# 4_Codec.net
KiCad netlist of a schematic drawn in Altium Designer
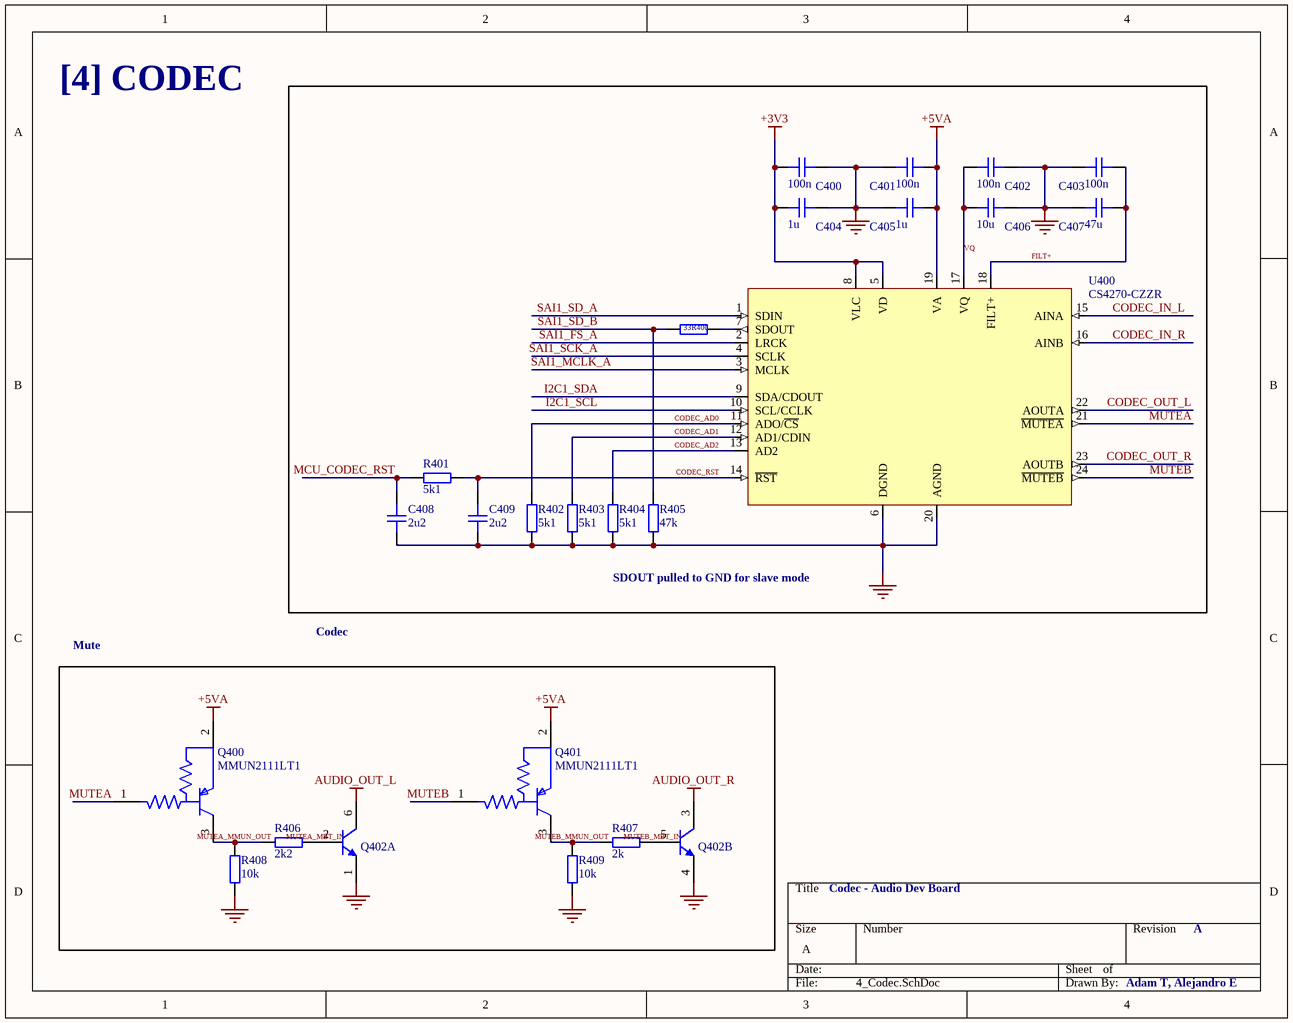
[diagram p0: 4_Codec.SchDoc]

(export (version "E")
  (design (tool "Eeschema 10.0.6"))
  (components
    (comp (ref "C400")
      (value "100n")
      (footprint "CAP_0402")
      (description "Capacitor SMD 0402")
      (libsource (lib "Schematic-Lib-PhilsLab") (part "CAP_0402"))
    )
    (comp (ref "C401")
      (value "100n")
      (footprint "CAP_0402")
      (description "Capacitor SMD 0402")
      (libsource (lib "Schematic-Lib-PhilsLab") (part "CAP_0402"))
    )
    (comp (ref "C402")
      (value "100n")
      (footprint "CAP_0402")
      (description "Capacitor SMD 0402")
      (libsource (lib "Schematic-Lib-PhilsLab") (part "CAP_0402"))
    )
    (comp (ref "C403")
      (value "100n")
      (footprint "CAP_0402")
      (description "Capacitor SMD 0402")
      (libsource (lib "Schematic-Lib-PhilsLab") (part "CAP_0402"))
    )
    (comp (ref "C404")
      (value "1u")
      (footprint "CAP_0603")
      (description "Capacitor SMD 0603")
      (libsource (lib "Schematic-Lib-PhilsLab") (part "CAP_0603"))
    )
    (comp (ref "C405")
      (value "1u")
      (footprint "CAP_0603")
      (description "Capacitor SMD 0603")
      (libsource (lib "Schematic-Lib-PhilsLab") (part "CAP_0603"))
    )
    (comp (ref "C406")
      (value "10u")
      (footprint "CAP_0603")
      (description "Capacitor SMD 0603")
      (libsource (lib "Schematic-Lib-PhilsLab") (part "CAP_0603"))
    )
    (comp (ref "C407")
      (value "47u")
      (footprint "CAP_1210")
      (description "Capacitor SMD 1210")
      (libsource (lib "Schematic-Lib-PhilsLab") (part "CAP_1210"))
    )
    (comp (ref "C408")
      (value "2u2")
      (footprint "CAP_0402")
      (description "Capacitor SMD 0402")
      (libsource (lib "Schematic-Lib-PhilsLab") (part "CAP_0402"))
    )
    (comp (ref "C409")
      (value "2u2")
      (footprint "CAP_0402")
      (description "Capacitor SMD 0402")
      (libsource (lib "Schematic-Lib-PhilsLab") (part "CAP_0402"))
    )
    (comp (ref "Q400")
      (value "MMUN2111LT1")
      (footprint "FP-318-08-MFG")
      (fields (field (name "VOLTAGE") "50V"))
      (libsource (lib "Altium Content Vault") (part "aca216ee67291743a5ff38348a4aab0"))
    )
    (comp (ref "Q401")
      (value "MMUN2111LT1")
      (footprint "FP-318-08-MFG")
      (fields (field (name "VOLTAGE") "50V"))
      (libsource (lib "Altium Content Vault") (part "aca216ee67291743a5ff38348a4aab0"))
    )
    (comp (ref "Q402")
      (value "MBT3904DW1T1G")
      (footprint "ONSC-SOT-363-6-419B-02_W_V")
      (description "Dual General Purpose Transistors, 6-Pin SOT-363, Pb-Free, Tape and Reel")
      (fields (field (name "MANUFACTURER") "On Semiconductor"))
      (libsource (lib "Altium Content Vault") (part "ONSC-NPN_NPN-6_F"))
    )
    (comp (ref "R400")
      (value "33")
      (footprint "RES_0402")
      (description "Resistor SMD 0402")
      (libsource (lib "Schematic-Lib-PhilsLab") (part "RES_0402"))
    )
    (comp (ref "R401")
      (value "5k1")
      (footprint "RES_0402")
      (description "Resistor SMD 0402")
      (libsource (lib "Schematic-Lib-PhilsLab") (part "RES_0402"))
    )
    (comp (ref "R402")
      (value "5k1")
      (footprint "RES_0402")
      (description "Resistor SMD 0402")
      (libsource (lib "Schematic-Lib-PhilsLab") (part "RES_0402"))
    )
    (comp (ref "R403")
      (value "5k1")
      (footprint "RES_0402")
      (description "Resistor SMD 0402")
      (libsource (lib "Schematic-Lib-PhilsLab") (part "RES_0402"))
    )
    (comp (ref "R404")
      (value "5k1")
      (footprint "RES_0402")
      (description "Resistor SMD 0402")
      (libsource (lib "Schematic-Lib-PhilsLab") (part "RES_0402"))
    )
    (comp (ref "R405")
      (value "47k")
      (footprint "RES_0402")
      (description "Resistor SMD 0402")
      (libsource (lib "Schematic-Lib-PhilsLab") (part "RES_0402"))
    )
    (comp (ref "R406")
      (value "2k2")
      (footprint "RES_0402")
      (description "Resistor SMD 0402")
      (libsource (lib "Schematic-Lib-PhilsLab") (part "RES_0402"))
    )
    (comp (ref "R407")
      (value "2k")
      (footprint "RES_0402")
      (description "Resistor SMD 0402")
      (libsource (lib "Schematic-Lib-PhilsLab") (part "RES_0402"))
    )
    (comp (ref "R408")
      (value "10k")
      (footprint "RES_0402")
      (description "Resistor SMD 0402")
      (libsource (lib "Schematic-Lib-PhilsLab") (part "RES_0402"))
    )
    (comp (ref "R409")
      (value "10k")
      (footprint "RES_0402")
      (description "Resistor SMD 0402")
      (libsource (lib "Schematic-Lib-PhilsLab") (part "RES_0402"))
    )
    (comp (ref "U400")
      (value "CS4270-CZZR")
      (footprint "TSSOP-24")
      (description "24-Bit 192kHz Stereo Audio Codec TSSOP-24")
      (fields (field (name "MANUFACTURER") "Cirrus Logic"))
      (libsource (lib "Schematic-Lib-PhilsLab") (part "CS4270-CZZR"))
    )
  )
  (nets
    (net (code "1") (name "+3V3") (class "Default")
      (node (ref "C400") (pin "1") (pinfunction "1_1") (pintype "passive"))
      (node (ref "C404") (pin "2") (pinfunction "2_2") (pintype "passive"))
      (node (ref "U400") (pin "5") (pinfunction "VD_5") (pintype "power_in"))
      (node (ref "U400") (pin "8") (pinfunction "VLC_8") (pintype "power_in"))
    )
    (net (code "2") (name "+5VA") (class "Default")
      (node (ref "C401") (pin "1") (pinfunction "1_1") (pintype "passive"))
      (node (ref "C405") (pin "2") (pinfunction "2_2") (pintype "passive"))
      (node (ref "Q400") (pin "2") (pinfunction "E_2") (pintype "passive"))
      (node (ref "Q401") (pin "2") (pinfunction "E_2") (pintype "passive"))
      (node (ref "U400") (pin "19") (pinfunction "VA_19") (pintype "power_in"))
    )
    (net (code "3") (name "/CODEC_AD0") (class "Default")
      (node (ref "R402") (pin "2") (pinfunction "2_2") (pintype "passive"))
      (node (ref "U400") (pin "11") (pinfunction "ADO/~{CS}_11") (pintype "input"))
    )
    (net (code "4") (name "/CODEC_AD1") (class "Default")
      (node (ref "R403") (pin "2") (pinfunction "2_2") (pintype "passive"))
      (node (ref "U400") (pin "12") (pinfunction "AD1/CDIN_12") (pintype "input"))
    )
    (net (code "5") (name "/CODEC_AD2") (class "Default")
      (node (ref "R404") (pin "2") (pinfunction "2_2") (pintype "passive"))
      (node (ref "U400") (pin "13") (pinfunction "AD2_13") (pintype "passive"))
    )
    (net (code "6") (name "/CODEC_IN_L") (class "Default")
      (node (ref "U400") (pin "15") (pinfunction "AINA_15") (pintype "input"))
    )
    (net (code "7") (name "/CODEC_IN_R") (class "Default")
      (node (ref "U400") (pin "16") (pinfunction "AINB_16") (pintype "input"))
    )
    (net (code "8") (name "/CODEC_OUT_L") (class "Default")
      (node (ref "U400") (pin "22") (pinfunction "AOUTA_22") (pintype "output"))
    )
    (net (code "9") (name "/CODEC_OUT_R") (class "Default")
      (node (ref "U400") (pin "23") (pinfunction "AOUTB_23") (pintype "output"))
    )
    (net (code "10") (name "/CODEC_RST") (class "Default")
      (node (ref "C409") (pin "2") (pinfunction "2_2") (pintype "passive"))
      (node (ref "R401") (pin "1") (pinfunction "1_1") (pintype "passive"))
      (node (ref "U400") (pin "14") (pinfunction "~{RST}_14") (pintype "input"))
    )
    (net (code "11") (name "/FILT+") (class "Default")
      (node (ref "C403") (pin "1") (pinfunction "1_1") (pintype "passive"))
      (node (ref "C407") (pin "2") (pinfunction "2_2") (pintype "passive"))
      (node (ref "U400") (pin "18") (pinfunction "FILT+_18") (pintype "power_in"))
    )
    (net (code "12") (name "/I2C1_SCL") (class "Default")
      (node (ref "U400") (pin "10") (pinfunction "SCL/CCLK_10") (pintype "input"))
    )
    (net (code "13") (name "/I2C1_SDA") (class "Default")
      (node (ref "U400") (pin "9") (pinfunction "SDA/CDOUT_9") (pintype "bidirectional"))
    )
    (net (code "14") (name "/MCU_CODEC_RST") (class "Default")
      (node (ref "C408") (pin "2") (pinfunction "2_2") (pintype "passive"))
      (node (ref "R401") (pin "2") (pinfunction "2_2") (pintype "passive"))
    )
    (net (code "15") (name "/MUTEA") (class "Default")
      (node (ref "Q400") (pin "1") (pinfunction "B_1") (pintype "passive"))
      (node (ref "U400") (pin "21") (pinfunction "~{MUTEA}_21") (pintype "output"))
    )
    (net (code "16") (name "/MUTEA_MBT_IN") (class "Default")
      (node (ref "Q402") (pin "2") (pinfunction "B_2") (pintype "passive"))
      (node (ref "R406") (pin "2") (pinfunction "2_2") (pintype "passive"))
    )
    (net (code "17") (name "/MUTEA_MMUN_OUT") (class "Default")
      (node (ref "Q400") (pin "3") (pinfunction "C_3") (pintype "passive"))
      (node (ref "R406") (pin "1") (pinfunction "1_1") (pintype "passive"))
      (node (ref "R408") (pin "2") (pinfunction "2_2") (pintype "passive"))
    )
    (net (code "18") (name "/MUTEB") (class "Default")
      (node (ref "Q401") (pin "1") (pinfunction "B_1") (pintype "passive"))
      (node (ref "U400") (pin "24") (pinfunction "~{MUTEB}_24") (pintype "output"))
    )
    (net (code "19") (name "/MUTEB_MBT_IN") (class "Default")
      (node (ref "Q402") (pin "5") (pinfunction "B_5") (pintype "passive"))
      (node (ref "R407") (pin "2") (pinfunction "2_2") (pintype "passive"))
    )
    (net (code "20") (name "/MUTEB_MMUN_OUT") (class "Default")
      (node (ref "Q401") (pin "3") (pinfunction "C_3") (pintype "passive"))
      (node (ref "R407") (pin "1") (pinfunction "1_1") (pintype "passive"))
      (node (ref "R409") (pin "2") (pinfunction "2_2") (pintype "passive"))
    )
    (net (code "21") (name "/SAI1_FS_A") (class "Default")
      (node (ref "U400") (pin "2") (pinfunction "LRCK_2") (pintype "bidirectional"))
    )
    (net (code "22") (name "/SAI1_MCLK_A") (class "Default")
      (node (ref "U400") (pin "3") (pinfunction "MCLK_3") (pintype "input"))
    )
    (net (code "23") (name "/SAI1_SCK_A") (class "Default")
      (node (ref "U400") (pin "4") (pinfunction "SCLK_4") (pintype "bidirectional"))
    )
    (net (code "24") (name "/SAI1_SD_A") (class "Default")
      (node (ref "U400") (pin "1") (pinfunction "SDIN_1") (pintype "input"))
    )
    (net (code "25") (name "/SAI1_SD_B") (class "Default")
      (node (ref "R400") (pin "1") (pinfunction "1_1") (pintype "passive"))
      (node (ref "R405") (pin "2") (pinfunction "2_2") (pintype "passive"))
    )
    (net (code "26") (name "/VQ") (class "Default")
      (node (ref "C402") (pin "1") (pinfunction "1_1") (pintype "passive"))
      (node (ref "C406") (pin "2") (pinfunction "2_2") (pintype "passive"))
      (node (ref "U400") (pin "17") (pinfunction "VQ_17") (pintype "power_in"))
    )
    (net (code "27") (name "AUDIO_OUT_L") (class "Default")
      (node (ref "Q402") (pin "6") (pinfunction "C_6") (pintype "passive"))
    )
    (net (code "28") (name "AUDIO_OUT_R") (class "Default")
      (node (ref "Q402") (pin "3") (pinfunction "C_3") (pintype "passive"))
    )
    (net (code "29") (name "GND") (class "Default")
      (node (ref "C400") (pin "2") (pinfunction "2_2") (pintype "passive"))
      (node (ref "C401") (pin "2") (pinfunction "2_2") (pintype "passive"))
      (node (ref "C402") (pin "2") (pinfunction "2_2") (pintype "passive"))
      (node (ref "C403") (pin "2") (pinfunction "2_2") (pintype "passive"))
      (node (ref "C404") (pin "1") (pinfunction "1_1") (pintype "passive"))
      (node (ref "C405") (pin "1") (pinfunction "1_1") (pintype "passive"))
      (node (ref "C406") (pin "1") (pinfunction "1_1") (pintype "passive"))
      (node (ref "C407") (pin "1") (pinfunction "1_1") (pintype "passive"))
      (node (ref "C408") (pin "1") (pinfunction "1_1") (pintype "passive"))
      (node (ref "C409") (pin "1") (pinfunction "1_1") (pintype "passive"))
      (node (ref "Q402") (pin "1") (pinfunction "E_1") (pintype "passive"))
      (node (ref "Q402") (pin "4") (pinfunction "E_4") (pintype "passive"))
      (node (ref "R402") (pin "1") (pinfunction "1_1") (pintype "passive"))
      (node (ref "R403") (pin "1") (pinfunction "1_1") (pintype "passive"))
      (node (ref "R404") (pin "1") (pinfunction "1_1") (pintype "passive"))
      (node (ref "R405") (pin "1") (pinfunction "1_1") (pintype "passive"))
      (node (ref "R408") (pin "1") (pinfunction "1_1") (pintype "passive"))
      (node (ref "R409") (pin "1") (pinfunction "1_1") (pintype "passive"))
      (node (ref "U400") (pin "20") (pinfunction "AGND_20") (pintype "power_in"))
      (node (ref "U400") (pin "6") (pinfunction "DGND_6") (pintype "power_in"))
    )
    (net (code "30") (name "Net-(U400-SDOUT)") (class "Default")
      (node (ref "R400") (pin "2") (pinfunction "2_2") (pintype "passive"))
      (node (ref "U400") (pin "7") (pinfunction "SDOUT_7") (pintype "output"))
    )
  )
)
